# Akhromsote.net
KiCad netlist of a schematic drawn in Altium Designer
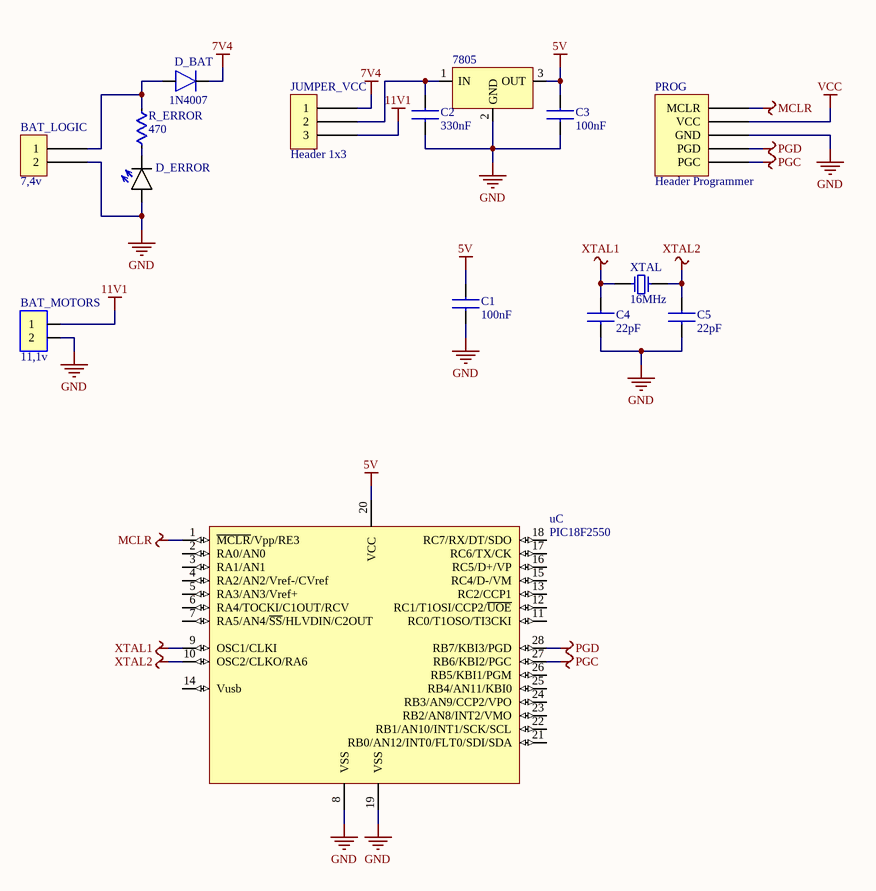
[diagram p0: Akhromsote.SchDoc]

(export (version "E")
  (design (tool "Eeschema 10.0.6"))
  (components
    (comp (ref "7805")
      (value "LM78XX")
      (footprint "TO-220-STRAIGHT")
      (libsource (lib "AltiumLibrary") (part "LM78XX"))
    )
    (comp (ref "BAT_LOGIC")
      (value "7,4v")
      (footprint "HEADER 1x2")
      (libsource (lib "AltiumLibrary") (part "Header 1x2"))
    )
    (comp (ref "BAT_MOTORS")
      (value "11,1v")
      (footprint "BLOCK_TERMINAL-2")
      (libsource (lib "AltiumLibrary") (part "2-BLOCK_TERMINAL"))
    )
    (comp (ref "C1")
      (value "100nF")
      (footprint "CAP-CER")
      (fields (field (name "Comment") "CAP-CER"))
      (libsource (lib "AltiumLibrary") (part "CAP-CER"))
    )
    (comp (ref "C2")
      (value "330nF")
      (footprint "CAP-CER")
      (fields (field (name "Comment") "CAP-CER"))
      (libsource (lib "AltiumLibrary") (part "CAP-CER"))
    )
    (comp (ref "C3")
      (value "100nF")
      (footprint "CAP-CER")
      (fields (field (name "Comment") "CAP-CER"))
      (libsource (lib "AltiumLibrary") (part "CAP-CER"))
    )
    (comp (ref "C4")
      (value "22pF")
      (footprint "CAP-CER")
      (fields (field (name "Comment") "CAP-CER"))
      (libsource (lib "AltiumLibrary") (part "CAP-CER"))
    )
    (comp (ref "C5")
      (value "22pF")
      (footprint "CAP-CER")
      (fields (field (name "Comment") "CAP-CER"))
      (libsource (lib "AltiumLibrary") (part "CAP-CER"))
    )
    (comp (ref "D_BAT")
      (value "DIODE")
      (footprint "DO-41")
      (fields (field (name "NAME") "1N4007"))
      (libsource (lib "AltiumLibrary") (part "DIODE"))
    )
    (comp (ref "D_ERROR")
      (value "LED")
      (footprint "LED-3MM-RED")
      (libsource (lib "AltiumLibrary") (part "LED"))
    )
    (comp (ref "JUMPER_VCC")
      (value "Header 1x3")
      (footprint "Header 1x3")
      (libsource (lib "AltiumLibrary") (part "Header 1x3"))
    )
    (comp (ref "PROG")
      (value "Header Programmer")
      (footprint "Header 1x5")
      (libsource (lib "AltiumLibrary") (part "Header Programmer"))
    )
    (comp (ref "R_ERROR")
      (value "470")
      (footprint "RES-Axial-400mil")
      (fields (field (name "Comment") "RES"))
      (libsource (lib "AltiumLibrary") (part "RES"))
    )
    (comp (ref "uC")
      (value "PIC18F2550")
      (footprint "DIP28")
      (libsource (lib "AltiumLibrary") (part "PIC18F2550"))
    )
    (comp (ref "XTAL")
      (value "XTAL")
      (footprint "HC-49/S")
      (fields (field (name "FREQUENCY") "16MHz"))
      (libsource (lib "AltiumLibrary") (part "XTAL"))
    )
  )
  (nets
    (net (code "1") (name "5V") (class "Default")
      (node (ref "7805") (pin "3") (pinfunction "OUT_3") (pintype "power_in"))
      (node (ref "C1") (pin "2") (pintype "passive"))
      (node (ref "C3") (pin "2") (pintype "passive"))
      (node (ref "uC") (pin "20") (pinfunction "VCC_20") (pintype "power_in"))
    )
    (net (code "2") (name "7V4") (class "Default")
      (node (ref "D_BAT") (pin "K") (pintype "passive"))
      (node (ref "JUMPER_VCC") (pin "1") (pinfunction "1_1") (pintype "passive"))
    )
    (net (code "3") (name "11V1") (class "Default")
      (node (ref "BAT_MOTORS") (pin "1") (pinfunction "1_1") (pintype "passive"))
      (node (ref "JUMPER_VCC") (pin "3") (pinfunction "3_3") (pintype "passive"))
    )
    (net (code "4") (name "GND") (class "Default")
      (node (ref "7805") (pin "2") (pinfunction "GND_2") (pintype "power_in"))
      (node (ref "BAT_LOGIC") (pin "2") (pinfunction "2_2") (pintype "passive"))
      (node (ref "BAT_MOTORS") (pin "2") (pinfunction "2_2") (pintype "passive"))
      (node (ref "C1") (pin "1") (pintype "passive"))
      (node (ref "C2") (pin "1") (pintype "passive"))
      (node (ref "C3") (pin "1") (pintype "passive"))
      (node (ref "C4") (pin "1") (pintype "passive"))
      (node (ref "C5") (pin "1") (pintype "passive"))
      (node (ref "D_ERROR") (pin "A") (pintype "passive"))
      (node (ref "PROG") (pin "3") (pinfunction "GND_3") (pintype "power_in"))
      (node (ref "uC") (pin "19") (pinfunction "VSS_19") (pintype "power_in"))
      (node (ref "uC") (pin "8") (pinfunction "VSS_8") (pintype "power_in"))
    )
    (net (code "5") (name "MCLR") (class "Default")
      (node (ref "PROG") (pin "1") (pinfunction "MCLR_1") (pintype "passive"))
      (node (ref "uC") (pin "1") (pinfunction "~{MCLR}/Vpp/RE3_1") (pintype "bidirectional"))
    )
    (net (code "6") (name "Net-(7805-IN)") (class "Default")
      (node (ref "7805") (pin "1") (pinfunction "IN_1") (pintype "power_in"))
      (node (ref "C2") (pin "2") (pintype "passive"))
      (node (ref "JUMPER_VCC") (pin "2") (pinfunction "2_2") (pintype "passive"))
    )
    (net (code "7") (name "Net-(BAT_LOGIC-Pad1)") (class "Default")
      (node (ref "BAT_LOGIC") (pin "1") (pinfunction "1_1") (pintype "passive"))
      (node (ref "D_BAT") (pin "A") (pintype "passive"))
      (node (ref "R_ERROR") (pin "2") (pintype "passive"))
    )
    (net (code "8") (name "Net-(D_ERROR-PadK)") (class "Default")
      (node (ref "D_ERROR") (pin "K") (pintype "passive"))
      (node (ref "R_ERROR") (pin "1") (pintype "passive"))
    )
    (net (code "9") (name "PGC") (class "Default")
      (node (ref "PROG") (pin "5") (pinfunction "PGC_5") (pintype "passive"))
      (node (ref "uC") (pin "27") (pinfunction "RB6/KBI2/PGC_27") (pintype "bidirectional"))
    )
    (net (code "10") (name "PGD") (class "Default")
      (node (ref "PROG") (pin "4") (pinfunction "PGD_4") (pintype "passive"))
      (node (ref "uC") (pin "28") (pinfunction "RB7/KBI3/PGD_28") (pintype "bidirectional"))
    )
    (net (code "11") (name "VCC") (class "Default")
      (node (ref "PROG") (pin "2") (pinfunction "VCC_2") (pintype "power_in"))
    )
    (net (code "12") (name "XTAL1") (class "Default")
      (node (ref "C4") (pin "2") (pintype "passive"))
      (node (ref "XTAL") (pin "2") (pintype "passive"))
      (node (ref "uC") (pin "9") (pinfunction "OSC1/CLKI_9") (pintype "bidirectional"))
    )
    (net (code "13") (name "XTAL2") (class "Default")
      (node (ref "C5") (pin "2") (pintype "passive"))
      (node (ref "XTAL") (pin "1") (pintype "passive"))
      (node (ref "uC") (pin "10") (pinfunction "OSC2/CLKO/RA6_10") (pintype "bidirectional"))
    )
    (net (code "14") (name "unconnected-(uC-RA0{slash}AN0-Pad2)") (class "Default")
      (node (ref "uC") (pin "2") (pinfunction "RA0/AN0_2") (pintype "bidirectional"))
    )
    (net (code "15") (name "unconnected-(uC-RA1{slash}AN1-Pad3)") (class "Default")
      (node (ref "uC") (pin "3") (pinfunction "RA1/AN1_3") (pintype "bidirectional"))
    )
    (net (code "16") (name "unconnected-(uC-RA2{slash}AN2{slash}Vref-{slash}CVref-Pad4)") (class "Default")
      (node (ref "uC") (pin "4") (pinfunction "RA2/AN2/Vref-/CVref_4") (pintype "bidirectional"))
    )
    (net (code "17") (name "unconnected-(uC-RA3{slash}AN3{slash}Vref+-Pad5)") (class "Default")
      (node (ref "uC") (pin "5") (pinfunction "RA3/AN3/Vref+_5") (pintype "bidirectional"))
    )
    (net (code "18") (name "unconnected-(uC-RA4{slash}TOCKI{slash}C1OUT{slash}RCV-Pad6)") (class "Default")
      (node (ref "uC") (pin "6") (pinfunction "RA4/TOCKI/C1OUT/RCV_6") (pintype "bidirectional"))
    )
    (net (code "19") (name "unconnected-(uC-RA5{slash}AN4{slash}~{SS}{slash}HLVDIN{slash}C2OUT-Pad7)") (class "Default")
      (node (ref "uC") (pin "7") (pinfunction "RA5/AN4/~{SS}/HLVDIN/C2OUT_7") (pintype "bidirectional"))
    )
    (net (code "20") (name "unconnected-(uC-RB0{slash}AN12{slash}INT0{slash}FLT0{slash}SDI{slash}SDA-Pad21)") (class "Default")
      (node (ref "uC") (pin "21") (pinfunction "RB0/AN12/INT0/FLT0/SDI/SDA_21") (pintype "bidirectional"))
    )
    (net (code "21") (name "unconnected-(uC-RB1{slash}AN10{slash}INT1{slash}SCK{slash}SCL-Pad22)") (class "Default")
      (node (ref "uC") (pin "22") (pinfunction "RB1/AN10/INT1/SCK/SCL_22") (pintype "bidirectional"))
    )
    (net (code "22") (name "unconnected-(uC-RB2{slash}AN8{slash}INT2{slash}VMO-Pad23)") (class "Default")
      (node (ref "uC") (pin "23") (pinfunction "RB2/AN8/INT2/VMO_23") (pintype "bidirectional"))
    )
    (net (code "23") (name "unconnected-(uC-RB3{slash}AN9{slash}CCP2{slash}VPO-Pad24)") (class "Default")
      (node (ref "uC") (pin "24") (pinfunction "RB3/AN9/CCP2/VPO_24") (pintype "bidirectional"))
    )
    (net (code "24") (name "unconnected-(uC-RB4{slash}AN11{slash}KBI0-Pad25)") (class "Default")
      (node (ref "uC") (pin "25") (pinfunction "RB4/AN11/KBI0_25") (pintype "bidirectional"))
    )
    (net (code "25") (name "unconnected-(uC-RB5{slash}KBI1{slash}PGM-Pad26)") (class "Default")
      (node (ref "uC") (pin "26") (pinfunction "RB5/KBI1/PGM_26") (pintype "bidirectional"))
    )
    (net (code "26") (name "unconnected-(uC-RC0{slash}T1OSO{slash}TI3CKI-Pad11)") (class "Default")
      (node (ref "uC") (pin "11") (pinfunction "RC0/T1OSO/TI3CKI_11") (pintype "bidirectional"))
    )
    (net (code "27") (name "unconnected-(uC-RC1{slash}T1OSI{slash}CCP2{slash}~{UOE}-Pad12)") (class "Default")
      (node (ref "uC") (pin "12") (pinfunction "RC1/T1OSI/CCP2/~{UOE}_12") (pintype "bidirectional"))
    )
    (net (code "28") (name "unconnected-(uC-RC2{slash}CCP1-Pad13)") (class "Default")
      (node (ref "uC") (pin "13") (pinfunction "RC2/CCP1_13") (pintype "bidirectional"))
    )
    (net (code "29") (name "unconnected-(uC-RC4{slash}D-{slash}VM-Pad15)") (class "Default")
      (node (ref "uC") (pin "15") (pinfunction "RC4/D-/VM_15") (pintype "bidirectional"))
    )
    (net (code "30") (name "unconnected-(uC-RC5{slash}D+{slash}VP-Pad16)") (class "Default")
      (node (ref "uC") (pin "16") (pinfunction "RC5/D+/VP_16") (pintype "bidirectional"))
    )
    (net (code "31") (name "unconnected-(uC-RC6{slash}TX{slash}CK-Pad17)") (class "Default")
      (node (ref "uC") (pin "17") (pinfunction "RC6/TX/CK_17") (pintype "bidirectional"))
    )
    (net (code "32") (name "unconnected-(uC-RC7{slash}RX{slash}DT{slash}SDO-Pad18)") (class "Default")
      (node (ref "uC") (pin "18") (pinfunction "RC7/RX/DT/SDO_18") (pintype "bidirectional"))
    )
    (net (code "33") (name "unconnected-(uC-Vusb-Pad14)") (class "Default")
      (node (ref "uC") (pin "14") (pinfunction "Vusb_14") (pintype "bidirectional"))
    )
  )
)
